# old_small_line.net
KiCad netlist of a schematic drawn in EAGLE
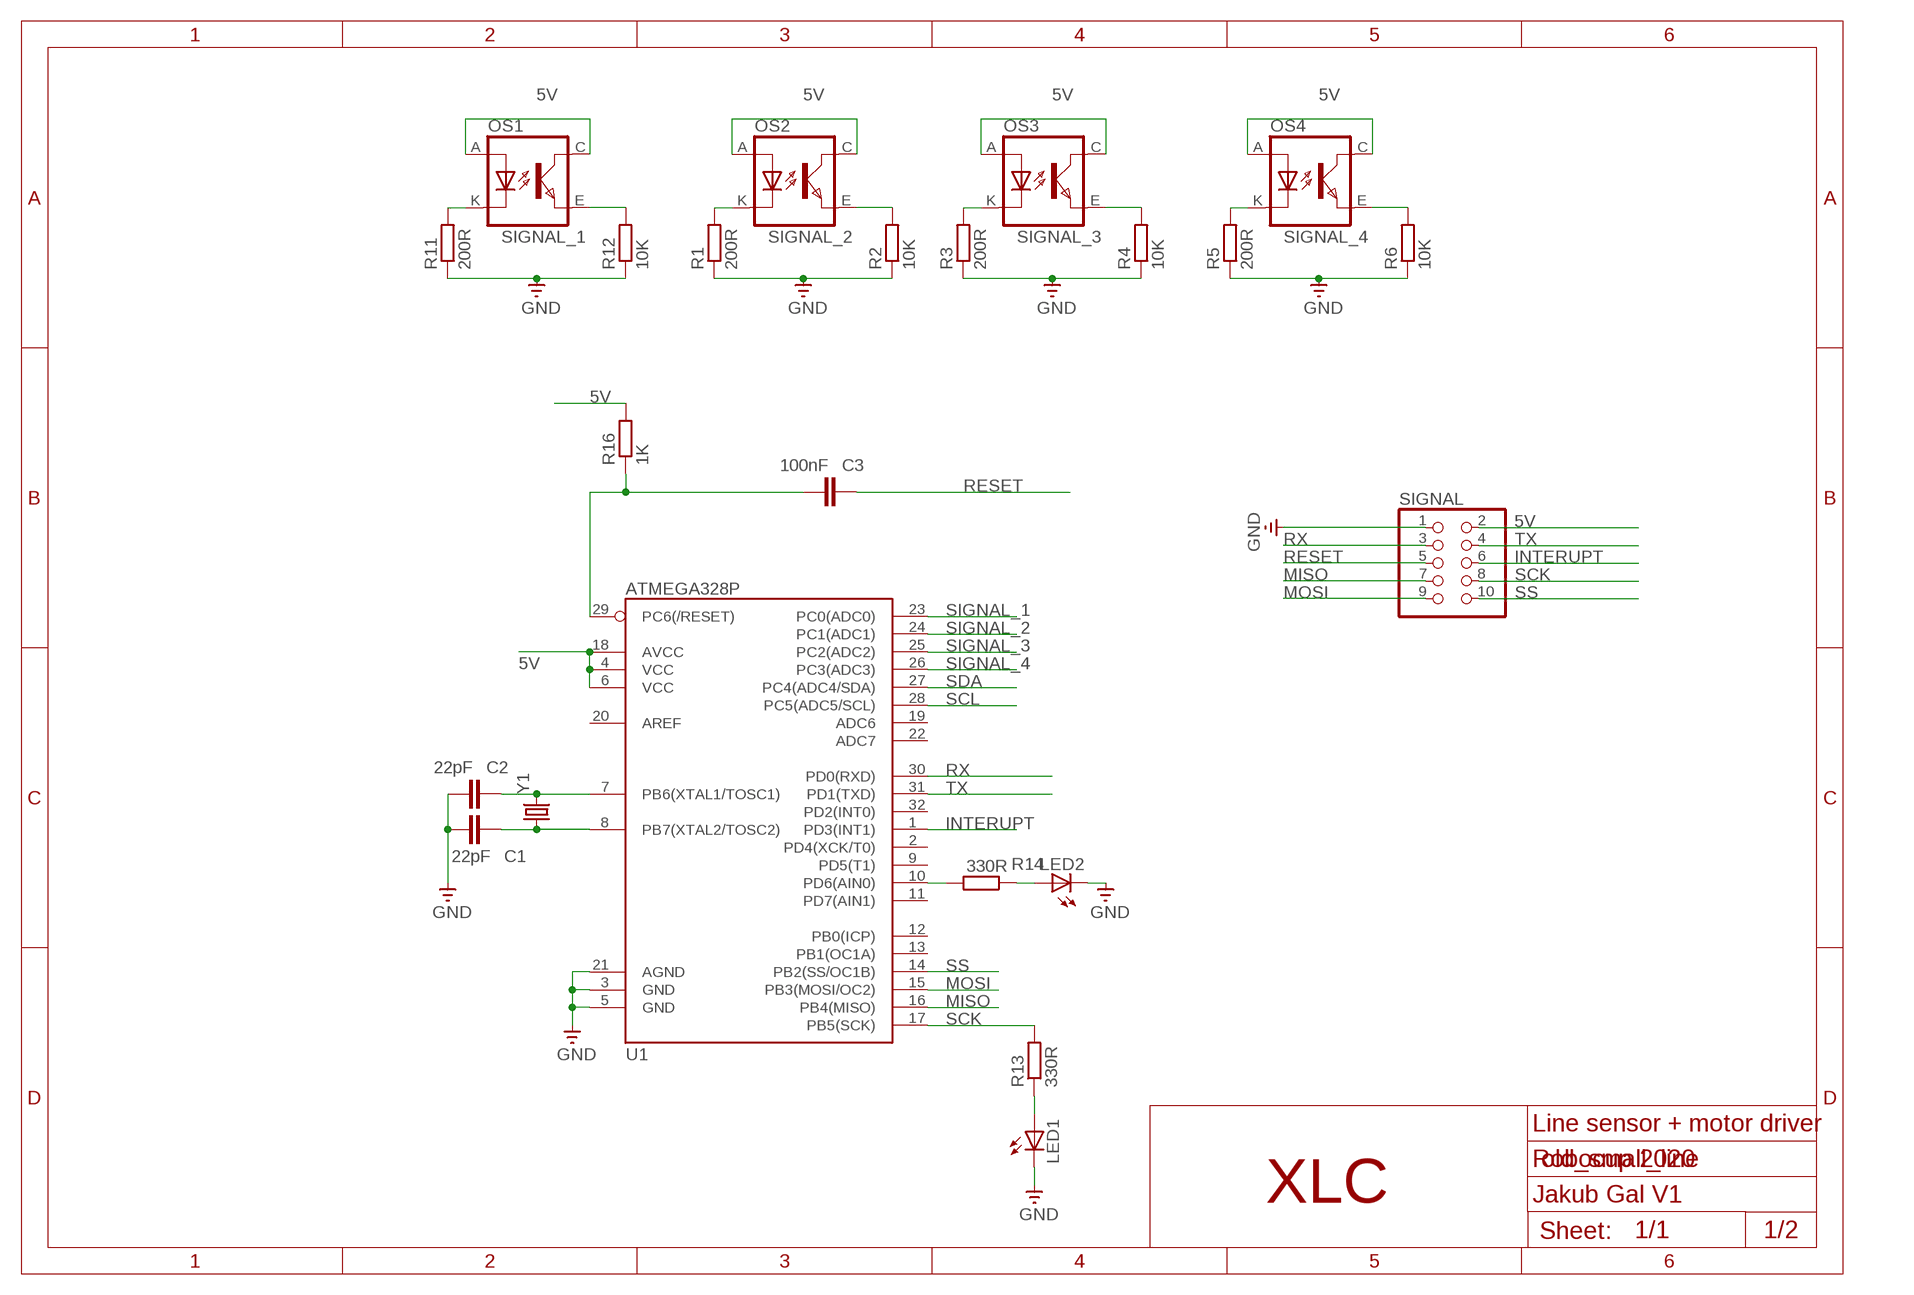
[diagram p0: schematic, sheet 1]

(export (version "E")
  (design (tool "Eeschema 10.0.6"))
  (components
    (comp (ref "C1")
      (value "22pF")
      (footprint "eagle-import:C0603")
      (libsource (lib "eagle-import") (part "C-EUC0603"))
    )
    (comp (ref "C2")
      (value "22pF")
      (footprint "eagle-import:C0603")
      (libsource (lib "eagle-import") (part "C-EUC0603"))
    )
    (comp (ref "C3")
      (value "100nF")
      (footprint "eagle-import:C0603")
      (libsource (lib "eagle-import") (part "C-EUC0603"))
    )
    (comp (ref "LED1")
      (value "LEDCHIPLED_0603")
      (footprint "eagle-import:CHIPLED_0603")
      (libsource (lib "eagle-import") (part "LEDCHIPLED_0603"))
    )
    (comp (ref "LED2")
      (value "LEDCHIPLED_0603")
      (footprint "eagle-import:CHIPLED_0603")
      (libsource (lib "eagle-import") (part "LEDCHIPLED_0603"))
    )
    (comp (ref "OS1")
      (value "TCRT5000")
      (footprint "eagle-import:TCRT5000")
      (libsource (lib "eagle-import") (part "TCRT5000"))
    )
    (comp (ref "OS2")
      (value "TCRT5000")
      (footprint "eagle-import:TCRT5000")
      (libsource (lib "eagle-import") (part "TCRT5000"))
    )
    (comp (ref "OS3")
      (value "TCRT5000")
      (footprint "eagle-import:TCRT5000")
      (libsource (lib "eagle-import") (part "TCRT5000"))
    )
    (comp (ref "OS4")
      (value "TCRT5000")
      (footprint "eagle-import:TCRT5000")
      (libsource (lib "eagle-import") (part "TCRT5000"))
    )
    (comp (ref "R1")
      (value "200R")
      (footprint "eagle-import:R0603")
      (libsource (lib "eagle-import") (part "R-EU_R0603"))
    )
    (comp (ref "R2")
      (value "10K")
      (footprint "eagle-import:R0603")
      (libsource (lib "eagle-import") (part "R-EU_R0603"))
    )
    (comp (ref "R3")
      (value "200R")
      (footprint "eagle-import:R0603")
      (libsource (lib "eagle-import") (part "R-EU_R0603"))
    )
    (comp (ref "R4")
      (value "10K")
      (footprint "eagle-import:R0603")
      (libsource (lib "eagle-import") (part "R-EU_R0603"))
    )
    (comp (ref "R5")
      (value "200R")
      (footprint "eagle-import:R0603")
      (libsource (lib "eagle-import") (part "R-EU_R0603"))
    )
    (comp (ref "R6")
      (value "10K")
      (footprint "eagle-import:R0603")
      (libsource (lib "eagle-import") (part "R-EU_R0603"))
    )
    (comp (ref "R11")
      (value "200R")
      (footprint "eagle-import:R0603")
      (libsource (lib "eagle-import") (part "R-EU_R0603"))
    )
    (comp (ref "R12")
      (value "10K")
      (footprint "eagle-import:R0603")
      (libsource (lib "eagle-import") (part "R-EU_R0603"))
    )
    (comp (ref "R13")
      (value "330R")
      (footprint "eagle-import:R0603")
      (libsource (lib "eagle-import") (part "R-EU_R0603"))
    )
    (comp (ref "R14")
      (value "330R")
      (footprint "eagle-import:R0603")
      (libsource (lib "eagle-import") (part "R-EU_R0603"))
    )
    (comp (ref "R16")
      (value "1K")
      (footprint "eagle-import:R0603")
      (libsource (lib "eagle-import") (part "R-EU_R0603"))
    )
    (comp (ref "SIGNAL")
      (value "PINHD-2X5")
      (footprint "eagle-import:2X05")
      (libsource (lib "eagle-import") (part "PINHD-2X5"))
    )
    (comp (ref "U1")
      (value "ATMEGA328P")
      (footprint "eagle-import:TQFP32-08")
      (libsource (lib "eagle-import") (part "ATMEGA328_SMT"))
    )
    (comp (ref "Y1")
      (value "CRYSTALHC49US")
      (footprint "eagle-import:HC49US")
      (libsource (lib "eagle-import") (part "CRYSTALHC49US"))
    )
  )
  (nets
    (net (code "1") (name "/5V") (class "Default")
      (node (ref "OS1") (pin "A") (pinfunction "ANODE_A") (pintype "passive"))
      (node (ref "OS1") (pin "C") (pinfunction "COLLECTOR_C") (pintype "passive"))
      (node (ref "OS2") (pin "A") (pinfunction "ANODE_A") (pintype "passive"))
      (node (ref "OS2") (pin "C") (pinfunction "COLLECTOR_C") (pintype "passive"))
      (node (ref "OS3") (pin "A") (pinfunction "ANODE_A") (pintype "passive"))
      (node (ref "OS3") (pin "C") (pinfunction "COLLECTOR_C") (pintype "passive"))
      (node (ref "OS4") (pin "A") (pinfunction "ANODE_A") (pintype "passive"))
      (node (ref "OS4") (pin "C") (pinfunction "COLLECTOR_C") (pintype "passive"))
      (node (ref "R16") (pin "2") (pinfunction "2_2") (pintype "passive"))
      (node (ref "SIGNAL") (pin "2") (pinfunction "2_2") (pintype "passive"))
      (node (ref "U1") (pin "18") (pinfunction "AVCC_18") (pintype "bidirectional"))
      (node (ref "U1") (pin "4") (pinfunction "VCC_4") (pintype "bidirectional"))
      (node (ref "U1") (pin "6") (pinfunction "VCC_6") (pintype "bidirectional"))
    )
    (net (code "2") (name "/INTERUPT") (class "Default")
      (node (ref "SIGNAL") (pin "6") (pinfunction "6_6") (pintype "passive"))
      (node (ref "U1") (pin "1") (pinfunction "PD3(INT1)_1") (pintype "bidirectional"))
    )
    (net (code "3") (name "/MISO") (class "Default")
      (node (ref "SIGNAL") (pin "7") (pinfunction "7_7") (pintype "passive"))
      (node (ref "U1") (pin "16") (pinfunction "PB4(MISO)_16") (pintype "bidirectional"))
    )
    (net (code "4") (name "/MOSI") (class "Default")
      (node (ref "SIGNAL") (pin "9") (pinfunction "9_9") (pintype "passive"))
      (node (ref "U1") (pin "15") (pinfunction "PB3(MOSI/OC2)_15") (pintype "bidirectional"))
    )
    (net (code "5") (name "/RESET") (class "Default")
      (node (ref "C3") (pin "2") (pinfunction "2_2") (pintype "passive"))
      (node (ref "SIGNAL") (pin "5") (pinfunction "5_5") (pintype "passive"))
    )
    (net (code "6") (name "/RX") (class "Default")
      (node (ref "SIGNAL") (pin "3") (pinfunction "3_3") (pintype "passive"))
      (node (ref "U1") (pin "30") (pinfunction "PD0(RXD)_30") (pintype "bidirectional"))
    )
    (net (code "7") (name "/SCK") (class "Default")
      (node (ref "R13") (pin "2") (pinfunction "2_2") (pintype "passive"))
      (node (ref "SIGNAL") (pin "8") (pinfunction "8_8") (pintype "passive"))
      (node (ref "U1") (pin "17") (pinfunction "PB5(SCK)_17") (pintype "bidirectional"))
    )
    (net (code "8") (name "/SCL") (class "Default")
      (node (ref "U1") (pin "28") (pinfunction "PC5(ADC5/SCL)_28") (pintype "bidirectional"))
    )
    (net (code "9") (name "/SDA") (class "Default")
      (node (ref "U1") (pin "27") (pinfunction "PC4(ADC4/SDA)_27") (pintype "bidirectional"))
    )
    (net (code "10") (name "/SIGNAL_1") (class "Default")
      (node (ref "OS1") (pin "E") (pinfunction "EMITTER_E") (pintype "passive"))
      (node (ref "R12") (pin "2") (pinfunction "2_2") (pintype "passive"))
      (node (ref "U1") (pin "23") (pinfunction "PC0(ADC0)_23") (pintype "bidirectional"))
    )
    (net (code "11") (name "/SIGNAL_2") (class "Default")
      (node (ref "OS2") (pin "E") (pinfunction "EMITTER_E") (pintype "passive"))
      (node (ref "R2") (pin "2") (pinfunction "2_2") (pintype "passive"))
      (node (ref "U1") (pin "24") (pinfunction "PC1(ADC1)_24") (pintype "bidirectional"))
    )
    (net (code "12") (name "/SIGNAL_3") (class "Default")
      (node (ref "OS3") (pin "E") (pinfunction "EMITTER_E") (pintype "passive"))
      (node (ref "R4") (pin "2") (pinfunction "2_2") (pintype "passive"))
      (node (ref "U1") (pin "25") (pinfunction "PC2(ADC2)_25") (pintype "bidirectional"))
    )
    (net (code "13") (name "/SIGNAL_4") (class "Default")
      (node (ref "OS4") (pin "E") (pinfunction "EMITTER_E") (pintype "passive"))
      (node (ref "R6") (pin "2") (pinfunction "2_2") (pintype "passive"))
      (node (ref "U1") (pin "26") (pinfunction "PC3(ADC3)_26") (pintype "bidirectional"))
    )
    (net (code "14") (name "/SS") (class "Default")
      (node (ref "SIGNAL") (pin "10") (pinfunction "10_10") (pintype "passive"))
      (node (ref "U1") (pin "14") (pinfunction "PB2(SS/OC1B)_14") (pintype "bidirectional"))
    )
    (net (code "15") (name "/TX") (class "Default")
      (node (ref "SIGNAL") (pin "4") (pinfunction "4_4") (pintype "passive"))
      (node (ref "U1") (pin "31") (pinfunction "PD1(TXD)_31") (pintype "bidirectional"))
    )
    (net (code "16") (name "GND") (class "Default")
      (node (ref "C1") (pin "1") (pinfunction "1_1") (pintype "passive"))
      (node (ref "C2") (pin "1") (pinfunction "1_1") (pintype "passive"))
      (node (ref "LED1") (pin "C") (pinfunction "C_C") (pintype "passive"))
      (node (ref "LED2") (pin "C") (pinfunction "C_C") (pintype "passive"))
      (node (ref "R1") (pin "1") (pinfunction "1_1") (pintype "passive"))
      (node (ref "R11") (pin "1") (pinfunction "1_1") (pintype "passive"))
      (node (ref "R12") (pin "1") (pinfunction "1_1") (pintype "passive"))
      (node (ref "R2") (pin "1") (pinfunction "1_1") (pintype "passive"))
      (node (ref "R3") (pin "1") (pinfunction "1_1") (pintype "passive"))
      (node (ref "R4") (pin "1") (pinfunction "1_1") (pintype "passive"))
      (node (ref "R5") (pin "1") (pinfunction "1_1") (pintype "passive"))
      (node (ref "R6") (pin "1") (pinfunction "1_1") (pintype "passive"))
      (node (ref "SIGNAL") (pin "1") (pinfunction "1_1") (pintype "passive"))
      (node (ref "U1") (pin "21") (pinfunction "AGND_21") (pintype "bidirectional"))
      (node (ref "U1") (pin "3") (pinfunction "GND_3") (pintype "bidirectional"))
      (node (ref "U1") (pin "5") (pinfunction "GND_5") (pintype "bidirectional"))
    )
    (net (code "17") (name "Net-(LED1-PadA)") (class "Default")
      (node (ref "LED1") (pin "A") (pinfunction "A_A") (pintype "passive"))
      (node (ref "R13") (pin "1") (pinfunction "1_1") (pintype "passive"))
    )
    (net (code "18") (name "Net-(LED2-PadA)") (class "Default")
      (node (ref "LED2") (pin "A") (pinfunction "A_A") (pintype "passive"))
      (node (ref "R14") (pin "1") (pinfunction "1_1") (pintype "passive"))
    )
    (net (code "19") (name "Net-(OS1-CATHODE)") (class "Default")
      (node (ref "OS1") (pin "K") (pinfunction "CATHODE_K") (pintype "passive"))
      (node (ref "R11") (pin "2") (pinfunction "2_2") (pintype "passive"))
    )
    (net (code "20") (name "Net-(OS2-CATHODE)") (class "Default")
      (node (ref "OS2") (pin "K") (pinfunction "CATHODE_K") (pintype "passive"))
      (node (ref "R1") (pin "2") (pinfunction "2_2") (pintype "passive"))
    )
    (net (code "21") (name "Net-(OS3-CATHODE)") (class "Default")
      (node (ref "OS3") (pin "K") (pinfunction "CATHODE_K") (pintype "passive"))
      (node (ref "R3") (pin "2") (pinfunction "2_2") (pintype "passive"))
    )
    (net (code "22") (name "Net-(OS4-CATHODE)") (class "Default")
      (node (ref "OS4") (pin "K") (pinfunction "CATHODE_K") (pintype "passive"))
      (node (ref "R5") (pin "2") (pinfunction "2_2") (pintype "passive"))
    )
    (net (code "23") (name "Net-(U1-PB6(XTAL1{slash}TOSC1))") (class "Default")
      (node (ref "C2") (pin "2") (pinfunction "2_2") (pintype "passive"))
      (node (ref "U1") (pin "7") (pinfunction "PB6(XTAL1/TOSC1)_7") (pintype "bidirectional"))
      (node (ref "Y1") (pin "2") (pinfunction "2_2") (pintype "passive"))
    )
    (net (code "24") (name "Net-(U1-PB7(XTAL2{slash}TOSC2))") (class "Default")
      (node (ref "C1") (pin "2") (pinfunction "2_2") (pintype "passive"))
      (node (ref "U1") (pin "8") (pinfunction "PB7(XTAL2/TOSC2)_8") (pintype "bidirectional"))
      (node (ref "Y1") (pin "1") (pinfunction "1_1") (pintype "passive"))
    )
    (net (code "25") (name "Net-(U1-PC6({slash}RESET))") (class "Default")
      (node (ref "C3") (pin "1") (pinfunction "1_1") (pintype "passive"))
      (node (ref "R16") (pin "1") (pinfunction "1_1") (pintype "passive"))
      (node (ref "U1") (pin "29") (pinfunction "PC6(/RESET)_29") (pintype "bidirectional"))
    )
    (net (code "26") (name "Net-(U1-PD6(AIN0))") (class "Default")
      (node (ref "R14") (pin "2") (pinfunction "2_2") (pintype "passive"))
      (node (ref "U1") (pin "10") (pinfunction "PD6(AIN0)_10") (pintype "bidirectional"))
    )
    (net (code "27") (name "unconnected-(U1-ADC6-Pad19)") (class "Default")
      (node (ref "U1") (pin "19") (pinfunction "ADC6_19") (pintype "bidirectional"))
    )
    (net (code "28") (name "unconnected-(U1-ADC7-Pad22)") (class "Default")
      (node (ref "U1") (pin "22") (pinfunction "ADC7_22") (pintype "bidirectional"))
    )
    (net (code "29") (name "unconnected-(U1-AREF-Pad20)") (class "Default")
      (node (ref "U1") (pin "20") (pinfunction "AREF_20") (pintype "bidirectional"))
    )
    (net (code "30") (name "unconnected-(U1-PB0(ICP)-Pad12)") (class "Default")
      (node (ref "U1") (pin "12") (pinfunction "PB0(ICP)_12") (pintype "bidirectional"))
    )
    (net (code "31") (name "unconnected-(U1-PB1(OC1A)-Pad13)") (class "Default")
      (node (ref "U1") (pin "13") (pinfunction "PB1(OC1A)_13") (pintype "bidirectional"))
    )
    (net (code "32") (name "unconnected-(U1-PD2(INT0)-Pad32)") (class "Default")
      (node (ref "U1") (pin "32") (pinfunction "PD2(INT0)_32") (pintype "bidirectional"))
    )
    (net (code "33") (name "unconnected-(U1-PD4(XCK{slash}T0)-Pad2)") (class "Default")
      (node (ref "U1") (pin "2") (pinfunction "PD4(XCK/T0)_2") (pintype "bidirectional"))
    )
    (net (code "34") (name "unconnected-(U1-PD5(T1)-Pad9)") (class "Default")
      (node (ref "U1") (pin "9") (pinfunction "PD5(T1)_9") (pintype "bidirectional"))
    )
    (net (code "35") (name "unconnected-(U1-PD7(AIN1)-Pad11)") (class "Default")
      (node (ref "U1") (pin "11") (pinfunction "PD7(AIN1)_11") (pintype "bidirectional"))
    )
  )
)
